# ProDoc_T527_LPDDR4_4__2024-06-06.net
KiCad netlist of a schematic drawn in EasyEDA Pro
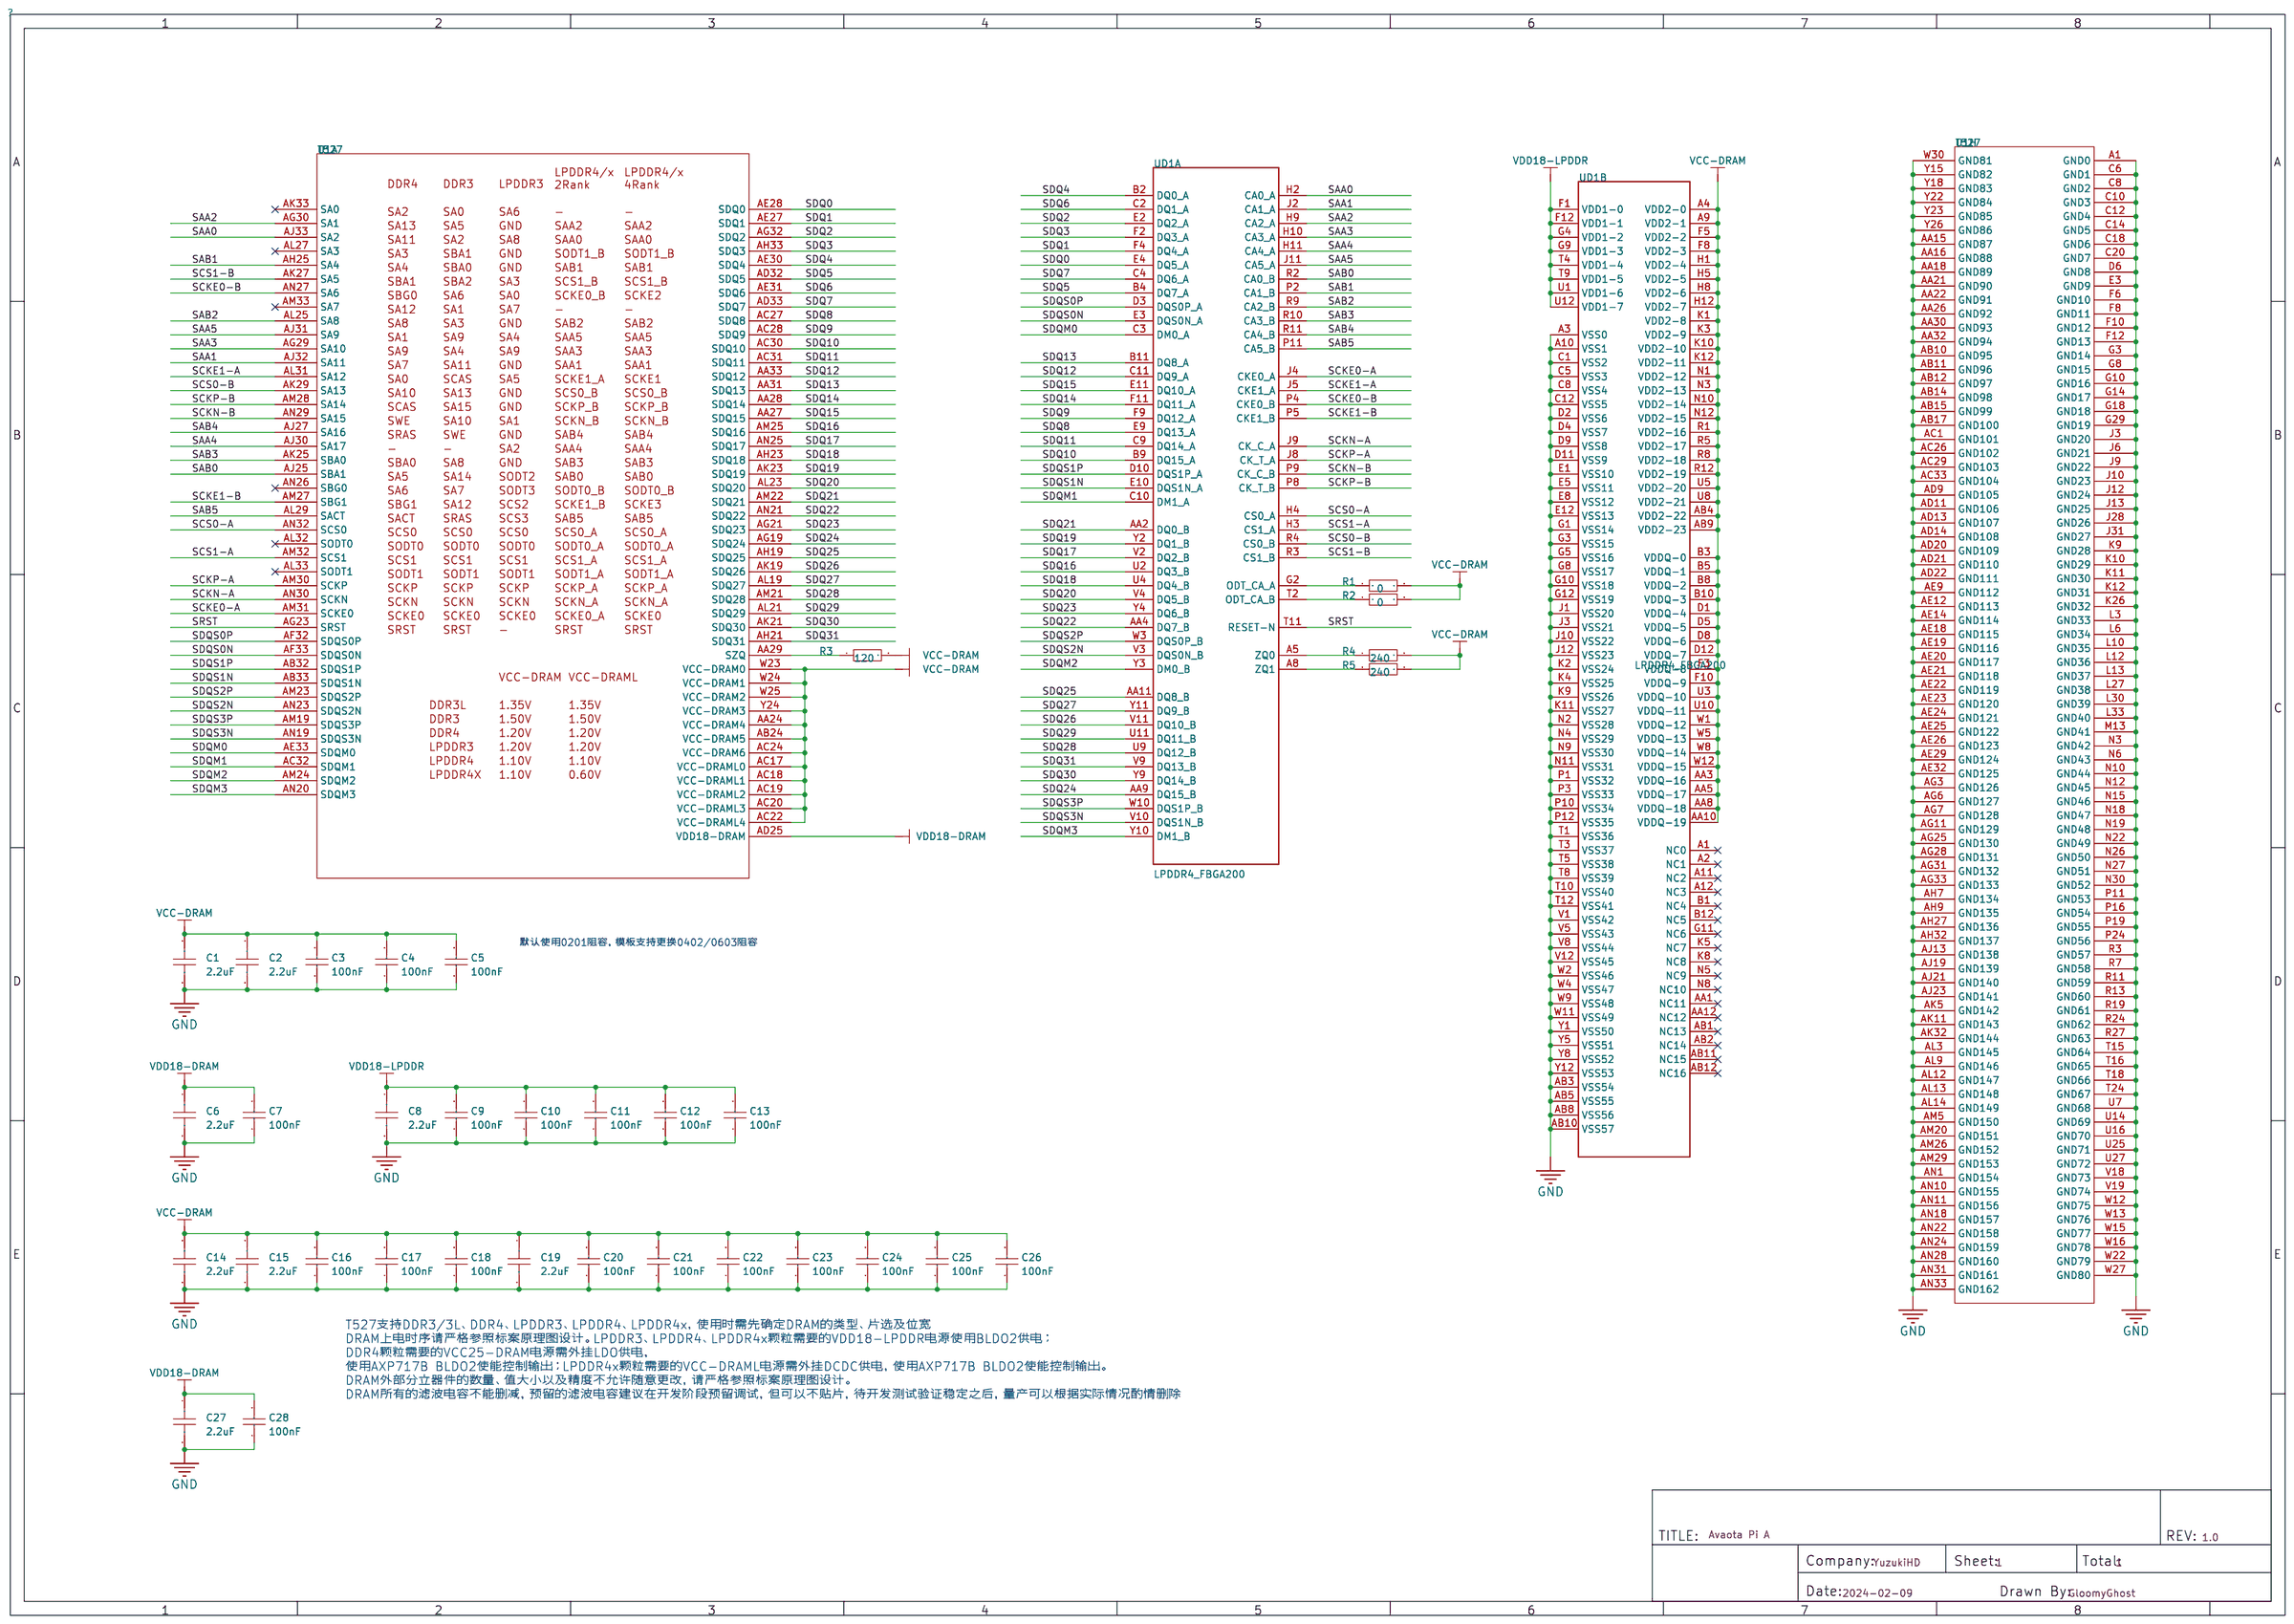
[diagram p0: schematic sheet]

(export (version "E")
  (design (tool "Eeschema 10.0.6"))
  (components
    (comp (ref "C1")
      (value "2.2uF")
      (footprint "easyedapro:C0201")
      (description "容值:2.2uF;精度:±20%;额定电压:6.3V;材质(温度系数):X5R;")
      (fields (field (name "Manufacturer Part") "0201X225M6R3NT") (field (name "Manufacturer") "FH(风华)"))
      (libsource (lib "easyedapro") (part "0201X225M6R3NT"))
    )
    (comp (ref "C2")
      (value "2.2uF")
      (footprint "easyedapro:C0201")
      (description "容值:2.2uF;精度:±20%;额定电压:6.3V;材质(温度系数):X5R;")
      (fields (field (name "Manufacturer Part") "0201X225M6R3NT") (field (name "Manufacturer") "FH(风华)"))
      (libsource (lib "easyedapro") (part "0201X225M6R3NT"))
    )
    (comp (ref "C3")
      (value "100nF")
      (footprint "easyedapro:C0201")
      (description "容值:100nF;精度:±10%;额定电压:10V;材质(温度系数):X5R;")
      (fields
        (field (name "Manufacturer Part") "GRM033R61A104KE15D")
        (field (name "Manufacturer") "muRata(村田)")
      )
      (libsource (lib "easyedapro") (part "GRM033R61A104KE15D"))
    )
    (comp (ref "C4")
      (value "100nF")
      (footprint "easyedapro:C0201")
      (description "容值:100nF;精度:±10%;额定电压:10V;材质(温度系数):X5R;")
      (fields
        (field (name "Manufacturer Part") "GRM033R61A104KE15D")
        (field (name "Manufacturer") "muRata(村田)")
      )
      (libsource (lib "easyedapro") (part "GRM033R61A104KE15D"))
    )
    (comp (ref "C5")
      (value "100nF")
      (footprint "easyedapro:C0201")
      (description "容值:100nF;精度:±10%;额定电压:10V;材质(温度系数):X5R;")
      (fields
        (field (name "Manufacturer Part") "GRM033R61A104KE15D")
        (field (name "Manufacturer") "muRata(村田)")
      )
      (libsource (lib "easyedapro") (part "GRM033R61A104KE15D"))
    )
    (comp (ref "C6")
      (value "2.2uF")
      (footprint "easyedapro:C0201")
      (description "容值:2.2uF;精度:±20%;额定电压:6.3V;材质(温度系数):X5R;")
      (fields (field (name "Manufacturer Part") "0201X225M6R3NT") (field (name "Manufacturer") "FH(风华)"))
      (libsource (lib "easyedapro") (part "0201X225M6R3NT"))
    )
    (comp (ref "C7")
      (value "100nF")
      (footprint "easyedapro:C0201")
      (description "容值:100nF;精度:±10%;额定电压:10V;材质(温度系数):X5R;")
      (fields
        (field (name "Manufacturer Part") "GRM033R61A104KE15D")
        (field (name "Manufacturer") "muRata(村田)")
      )
      (libsource (lib "easyedapro") (part "GRM033R61A104KE15D"))
    )
    (comp (ref "C8")
      (value "2.2uF")
      (footprint "easyedapro:C0201")
      (description "容值:2.2uF;精度:±20%;额定电压:6.3V;材质(温度系数):X5R;")
      (fields (field (name "Manufacturer Part") "0201X225M6R3NT") (field (name "Manufacturer") "FH(风华)"))
      (libsource (lib "easyedapro") (part "0201X225M6R3NT"))
    )
    (comp (ref "C9")
      (value "100nF")
      (footprint "easyedapro:C0201")
      (description "容值:100nF;精度:±10%;额定电压:10V;材质(温度系数):X5R;")
      (fields
        (field (name "Manufacturer Part") "GRM033R61A104KE15D")
        (field (name "Manufacturer") "muRata(村田)")
      )
      (libsource (lib "easyedapro") (part "GRM033R61A104KE15D"))
    )
    (comp (ref "C10")
      (value "100nF")
      (footprint "easyedapro:C0201")
      (description "容值:100nF;精度:±10%;额定电压:10V;材质(温度系数):X5R;")
      (fields
        (field (name "Manufacturer Part") "GRM033R61A104KE15D")
        (field (name "Manufacturer") "muRata(村田)")
      )
      (libsource (lib "easyedapro") (part "GRM033R61A104KE15D"))
    )
    (comp (ref "C11")
      (value "100nF")
      (footprint "easyedapro:C0201")
      (description "容值:100nF;精度:±10%;额定电压:10V;材质(温度系数):X5R;")
      (fields
        (field (name "Manufacturer Part") "GRM033R61A104KE15D")
        (field (name "Manufacturer") "muRata(村田)")
      )
      (libsource (lib "easyedapro") (part "GRM033R61A104KE15D"))
    )
    (comp (ref "C12")
      (value "100nF")
      (footprint "easyedapro:C0201")
      (description "容值:100nF;精度:±10%;额定电压:10V;材质(温度系数):X5R;")
      (fields
        (field (name "Manufacturer Part") "GRM033R61A104KE15D")
        (field (name "Manufacturer") "muRata(村田)")
      )
      (libsource (lib "easyedapro") (part "GRM033R61A104KE15D"))
    )
    (comp (ref "C13")
      (value "100nF")
      (footprint "easyedapro:C0201")
      (description "容值:100nF;精度:±10%;额定电压:10V;材质(温度系数):X5R;")
      (fields
        (field (name "Manufacturer Part") "GRM033R61A104KE15D")
        (field (name "Manufacturer") "muRata(村田)")
      )
      (libsource (lib "easyedapro") (part "GRM033R61A104KE15D"))
    )
    (comp (ref "C14")
      (value "2.2uF")
      (footprint "easyedapro:C0201")
      (description "容值:2.2uF;精度:±20%;额定电压:6.3V;材质(温度系数):X5R;")
      (fields (field (name "Manufacturer Part") "0201X225M6R3NT") (field (name "Manufacturer") "FH(风华)"))
      (libsource (lib "easyedapro") (part "0201X225M6R3NT"))
    )
    (comp (ref "C15")
      (value "2.2uF")
      (footprint "easyedapro:C0201")
      (description "容值:2.2uF;精度:±20%;额定电压:6.3V;材质(温度系数):X5R;")
      (fields (field (name "Manufacturer Part") "0201X225M6R3NT") (field (name "Manufacturer") "FH(风华)"))
      (libsource (lib "easyedapro") (part "0201X225M6R3NT"))
    )
    (comp (ref "C16")
      (value "100nF")
      (footprint "easyedapro:C0201")
      (description "容值:100nF;精度:±10%;额定电压:10V;材质(温度系数):X5R;")
      (fields
        (field (name "Manufacturer Part") "GRM033R61A104KE15D")
        (field (name "Manufacturer") "muRata(村田)")
      )
      (libsource (lib "easyedapro") (part "GRM033R61A104KE15D"))
    )
    (comp (ref "C17")
      (value "100nF")
      (footprint "easyedapro:C0201")
      (description "容值:100nF;精度:±10%;额定电压:10V;材质(温度系数):X5R;")
      (fields
        (field (name "Manufacturer Part") "GRM033R61A104KE15D")
        (field (name "Manufacturer") "muRata(村田)")
      )
      (libsource (lib "easyedapro") (part "GRM033R61A104KE15D"))
    )
    (comp (ref "C18")
      (value "100nF")
      (footprint "easyedapro:C0201")
      (description "容值:100nF;精度:±10%;额定电压:10V;材质(温度系数):X5R;")
      (fields
        (field (name "Manufacturer Part") "GRM033R61A104KE15D")
        (field (name "Manufacturer") "muRata(村田)")
      )
      (libsource (lib "easyedapro") (part "GRM033R61A104KE15D"))
    )
    (comp (ref "C19")
      (value "2.2uF")
      (footprint "easyedapro:C0201")
      (description "容值:2.2uF;精度:±20%;额定电压:6.3V;材质(温度系数):X5R;")
      (fields (field (name "Manufacturer Part") "0201X225M6R3NT") (field (name "Manufacturer") "FH(风华)"))
      (libsource (lib "easyedapro") (part "0201X225M6R3NT"))
    )
    (comp (ref "C20")
      (value "100nF")
      (footprint "easyedapro:C0201")
      (description "容值:100nF;精度:±10%;额定电压:10V;材质(温度系数):X5R;")
      (fields
        (field (name "Manufacturer Part") "GRM033R61A104KE15D")
        (field (name "Manufacturer") "muRata(村田)")
      )
      (libsource (lib "easyedapro") (part "GRM033R61A104KE15D"))
    )
    (comp (ref "C21")
      (value "100nF")
      (footprint "easyedapro:C0201")
      (description "容值:100nF;精度:±10%;额定电压:10V;材质(温度系数):X5R;")
      (fields
        (field (name "Manufacturer Part") "GRM033R61A104KE15D")
        (field (name "Manufacturer") "muRata(村田)")
      )
      (libsource (lib "easyedapro") (part "GRM033R61A104KE15D"))
    )
    (comp (ref "C22")
      (value "100nF")
      (footprint "easyedapro:C0201")
      (description "容值:100nF;精度:±10%;额定电压:10V;材质(温度系数):X5R;")
      (fields
        (field (name "Manufacturer Part") "GRM033R61A104KE15D")
        (field (name "Manufacturer") "muRata(村田)")
      )
      (libsource (lib "easyedapro") (part "GRM033R61A104KE15D"))
    )
    (comp (ref "C23")
      (value "100nF")
      (footprint "easyedapro:C0201")
      (description "容值:100nF;精度:±10%;额定电压:10V;材质(温度系数):X5R;")
      (fields
        (field (name "Manufacturer Part") "GRM033R61A104KE15D")
        (field (name "Manufacturer") "muRata(村田)")
      )
      (libsource (lib "easyedapro") (part "GRM033R61A104KE15D"))
    )
    (comp (ref "C24")
      (value "100nF")
      (footprint "easyedapro:C0201")
      (description "容值:100nF;精度:±10%;额定电压:10V;材质(温度系数):X5R;")
      (fields
        (field (name "Manufacturer Part") "GRM033R61A104KE15D")
        (field (name "Manufacturer") "muRata(村田)")
      )
      (libsource (lib "easyedapro") (part "GRM033R61A104KE15D"))
    )
    (comp (ref "C25")
      (value "100nF")
      (footprint "easyedapro:C0201")
      (description "容值:100nF;精度:±10%;额定电压:10V;材质(温度系数):X5R;")
      (fields
        (field (name "Manufacturer Part") "GRM033R61A104KE15D")
        (field (name "Manufacturer") "muRata(村田)")
      )
      (libsource (lib "easyedapro") (part "GRM033R61A104KE15D"))
    )
    (comp (ref "C26")
      (value "100nF")
      (footprint "easyedapro:C0201")
      (description "容值:100nF;精度:±10%;额定电压:10V;材质(温度系数):X5R;")
      (fields
        (field (name "Manufacturer Part") "GRM033R61A104KE15D")
        (field (name "Manufacturer") "muRata(村田)")
      )
      (libsource (lib "easyedapro") (part "GRM033R61A104KE15D"))
    )
    (comp (ref "C27")
      (value "2.2uF")
      (footprint "easyedapro:C0201")
      (description "容值:2.2uF;精度:±20%;额定电压:6.3V;材质(温度系数):X5R;")
      (fields (field (name "Manufacturer Part") "0201X225M6R3NT") (field (name "Manufacturer") "FH(风华)"))
      (libsource (lib "easyedapro") (part "0201X225M6R3NT"))
    )
    (comp (ref "C28")
      (value "100nF")
      (footprint "easyedapro:C0201")
      (description "容值:100nF;精度:±10%;额定电压:10V;材质(温度系数):X5R;")
      (fields
        (field (name "Manufacturer Part") "GRM033R61A104KE15D")
        (field (name "Manufacturer") "muRata(村田)")
      )
      (libsource (lib "easyedapro") (part "GRM033R61A104KE15D"))
    )
    (comp (ref "R1") (value "0") (footprint "easyedapro:R0201") (libsource (lib "easyedapro") (part "电阻")))
    (comp (ref "R2") (value "0") (footprint "easyedapro:R0201") (libsource (lib "easyedapro") (part "电阻")))
    (comp (ref "R3") (value "120") (footprint "easyedapro:R0201") (libsource (lib "easyedapro") (part "电阻")))
    (comp (ref "R4") (value "240") (footprint "easyedapro:R0201") (libsource (lib "easyedapro") (part "电阻")))
    (comp (ref "R5") (value "240") (footprint "easyedapro:R0201") (libsource (lib "easyedapro") (part "电阻")))
    (comp (ref "U1")
      (value "T527")
      (footprint "easyedapro:T527-BGA664")
      (description "Allwinner T527 SoC")
      (libsource (lib "easyedapro") (part "T527"))
    )
    (comp (ref "UD1")
      (value "LPDDR4_FBGA200")
      (footprint "easyedapro:BGA200P65_80B1000_1500H90")
      (libsource (lib "easyedapro") (part "LPDDR4_FBGA200"))
    )
  )
  (nets
    (net (code "1") (name "/SAA0") (class "Default")
      (node (ref "U1") (pin "AJ33") (pinfunction "SA2_AJ33") (pintype "input"))
      (node (ref "UD1") (pin "H2") (pinfunction "CA0_A_H2") (pintype "input"))
    )
    (net (code "2") (name "/SAA1") (class "Default")
      (node (ref "U1") (pin "AJ32") (pinfunction "SA11_AJ32") (pintype "input"))
      (node (ref "UD1") (pin "J2") (pinfunction "CA1_A_J2") (pintype "input"))
    )
    (net (code "3") (name "/SAA2") (class "Default")
      (node (ref "U1") (pin "AG30") (pinfunction "SA1_AG30") (pintype "input"))
      (node (ref "UD1") (pin "H9") (pinfunction "CA2_A_H9") (pintype "input"))
    )
    (net (code "4") (name "/SAA3") (class "Default")
      (node (ref "U1") (pin "AG29") (pinfunction "SA10_AG29") (pintype "input"))
      (node (ref "UD1") (pin "H10") (pinfunction "CA3_A_H10") (pintype "input"))
    )
    (net (code "5") (name "/SAA4") (class "Default")
      (node (ref "U1") (pin "AJ30") (pinfunction "SA17_AJ30") (pintype "input"))
      (node (ref "UD1") (pin "H11") (pinfunction "CA4_A_H11") (pintype "input"))
    )
    (net (code "6") (name "/SAA5") (class "Default")
      (node (ref "U1") (pin "AJ31") (pinfunction "SA9_AJ31") (pintype "input"))
      (node (ref "UD1") (pin "J11") (pinfunction "CA5_A_J11") (pintype "input"))
    )
    (net (code "7") (name "/SAB0") (class "Default")
      (node (ref "U1") (pin "AJ25") (pinfunction "SBA1_AJ25") (pintype "input"))
      (node (ref "UD1") (pin "R2") (pinfunction "CA0_B_R2") (pintype "input"))
    )
    (net (code "8") (name "/SAB1") (class "Default")
      (node (ref "U1") (pin "AH25") (pinfunction "SA4_AH25") (pintype "input"))
      (node (ref "UD1") (pin "P2") (pinfunction "CA1_B_P2") (pintype "input"))
    )
    (net (code "9") (name "/SAB2") (class "Default")
      (node (ref "U1") (pin "AL25") (pinfunction "SA8_AL25") (pintype "input"))
      (node (ref "UD1") (pin "R9") (pinfunction "CA2_B_R9") (pintype "input"))
    )
    (net (code "10") (name "/SAB3") (class "Default")
      (node (ref "U1") (pin "AK25") (pinfunction "SBA0_AK25") (pintype "input"))
      (node (ref "UD1") (pin "R10") (pinfunction "CA3_B_R10") (pintype "input"))
    )
    (net (code "11") (name "/SAB4") (class "Default")
      (node (ref "U1") (pin "AJ27") (pinfunction "SA16_AJ27") (pintype "input"))
      (node (ref "UD1") (pin "R11") (pinfunction "CA4_B_R11") (pintype "input"))
    )
    (net (code "12") (name "/SAB5") (class "Default")
      (node (ref "U1") (pin "AL29") (pinfunction "SACT_AL29") (pintype "input"))
      (node (ref "UD1") (pin "P11") (pinfunction "CA5_B_P11") (pintype "input"))
    )
    (net (code "13") (name "/SCKE0-A") (class "Default")
      (node (ref "U1") (pin "AM31") (pinfunction "SCKE0_AM31") (pintype "input"))
      (node (ref "UD1") (pin "J4") (pinfunction "CKE0_A_J4") (pintype "input"))
    )
    (net (code "14") (name "/SCKE0-B") (class "Default")
      (node (ref "U1") (pin "AN27") (pinfunction "SA6_AN27") (pintype "input"))
      (node (ref "UD1") (pin "P4") (pinfunction "CKE0_B_P4") (pintype "input"))
    )
    (net (code "15") (name "/SCKE1-A") (class "Default")
      (node (ref "U1") (pin "AL31") (pinfunction "SA12_AL31") (pintype "input"))
      (node (ref "UD1") (pin "J5") (pinfunction "CKE1_A_J5") (pintype "input"))
    )
    (net (code "16") (name "/SCKE1-B") (class "Default")
      (node (ref "U1") (pin "AM27") (pinfunction "SBG1_AM27") (pintype "input"))
      (node (ref "UD1") (pin "P5") (pinfunction "CKE1_B_P5") (pintype "input"))
    )
    (net (code "17") (name "/SCKN-A") (class "Default")
      (node (ref "U1") (pin "AN30") (pinfunction "SCKN_AN30") (pintype "input"))
      (node (ref "UD1") (pin "J9") (pinfunction "CK_C_A_J9") (pintype "input"))
    )
    (net (code "18") (name "/SCKN-B") (class "Default")
      (node (ref "U1") (pin "AN29") (pinfunction "SA15_AN29") (pintype "input"))
      (node (ref "UD1") (pin "P9") (pinfunction "CK_C_B_P9") (pintype "input"))
    )
    (net (code "19") (name "/SCKP-A") (class "Default")
      (node (ref "U1") (pin "AM30") (pinfunction "SCKP_AM30") (pintype "input"))
      (node (ref "UD1") (pin "J8") (pinfunction "CK_T_A_J8") (pintype "input"))
    )
    (net (code "20") (name "/SCKP-B") (class "Default")
      (node (ref "U1") (pin "AM28") (pinfunction "SA14_AM28") (pintype "input"))
      (node (ref "UD1") (pin "P8") (pinfunction "CK_T_B_P8") (pintype "input"))
    )
    (net (code "21") (name "/SCS0-A") (class "Default")
      (node (ref "U1") (pin "AN32") (pinfunction "SCS0_AN32") (pintype "input"))
      (node (ref "UD1") (pin "H4") (pinfunction "CS0_A_H4") (pintype "input"))
    )
    (net (code "22") (name "/SCS0-B") (class "Default")
      (node (ref "U1") (pin "AK29") (pinfunction "SA13_AK29") (pintype "input"))
      (node (ref "UD1") (pin "R4") (pinfunction "CS0_B_R4") (pintype "input"))
    )
    (net (code "23") (name "/SCS1-A") (class "Default")
      (node (ref "U1") (pin "AM32") (pinfunction "SCS1_AM32") (pintype "input"))
      (node (ref "UD1") (pin "H3") (pinfunction "CS1_A_H3") (pintype "input"))
    )
    (net (code "24") (name "/SCS1-B") (class "Default")
      (node (ref "U1") (pin "AK27") (pinfunction "SA5_AK27") (pintype "input"))
      (node (ref "UD1") (pin "R3") (pinfunction "CS1_B_R3") (pintype "input"))
    )
    (net (code "25") (name "/SDQ0") (class "Default")
      (node (ref "U1") (pin "AE28") (pinfunction "SDQ0_AE28") (pintype "input"))
      (node (ref "UD1") (pin "E4") (pinfunction "DQ5_A_E4") (pintype "input"))
    )
    (net (code "26") (name "/SDQ1") (class "Default")
      (node (ref "U1") (pin "AE27") (pinfunction "SDQ1_AE27") (pintype "input"))
      (node (ref "UD1") (pin "F4") (pinfunction "DQ4_A_F4") (pintype "input"))
    )
    (net (code "27") (name "/SDQ2") (class "Default")
      (node (ref "U1") (pin "AG32") (pinfunction "SDQ2_AG32") (pintype "input"))
      (node (ref "UD1") (pin "E2") (pinfunction "DQ2_A_E2") (pintype "input"))
    )
    (net (code "28") (name "/SDQ3") (class "Default")
      (node (ref "U1") (pin "AH33") (pinfunction "SDQ3_AH33") (pintype "input"))
      (node (ref "UD1") (pin "F2") (pinfunction "DQ3_A_F2") (pintype "input"))
    )
    (net (code "29") (name "/SDQ4") (class "Default")
      (node (ref "U1") (pin "AE30") (pinfunction "SDQ4_AE30") (pintype "input"))
      (node (ref "UD1") (pin "B2") (pinfunction "DQ0_A_B2") (pintype "input"))
    )
    (net (code "30") (name "/SDQ5") (class "Default")
      (node (ref "U1") (pin "AD32") (pinfunction "SDQ5_AD32") (pintype "input"))
      (node (ref "UD1") (pin "B4") (pinfunction "DQ7_A_B4") (pintype "input"))
    )
    (net (code "31") (name "/SDQ6") (class "Default")
      (node (ref "U1") (pin "AE31") (pinfunction "SDQ6_AE31") (pintype "input"))
      (node (ref "UD1") (pin "C2") (pinfunction "DQ1_A_C2") (pintype "input"))
    )
    (net (code "32") (name "/SDQ7") (class "Default")
      (node (ref "U1") (pin "AD33") (pinfunction "SDQ7_AD33") (pintype "input"))
      (node (ref "UD1") (pin "C4") (pinfunction "DQ6_A_C4") (pintype "input"))
    )
    (net (code "33") (name "/SDQ8") (class "Default")
      (node (ref "U1") (pin "AC27") (pinfunction "SDQ8_AC27") (pintype "input"))
      (node (ref "UD1") (pin "E9") (pinfunction "DQ13_A_E9") (pintype "input"))
    )
    (net (code "34") (name "/SDQ9") (class "Default")
      (node (ref "U1") (pin "AC28") (pinfunction "SDQ9_AC28") (pintype "input"))
      (node (ref "UD1") (pin "F9") (pinfunction "DQ12_A_F9") (pintype "input"))
    )
    (net (code "35") (name "/SDQ10") (class "Default")
      (node (ref "U1") (pin "AC30") (pinfunction "SDQ10_AC30") (pintype "input"))
      (node (ref "UD1") (pin "B9") (pinfunction "DQ15_A_B9") (pintype "input"))
    )
    (net (code "36") (name "/SDQ11") (class "Default")
      (node (ref "U1") (pin "AC31") (pinfunction "SDQ11_AC31") (pintype "input"))
      (node (ref "UD1") (pin "C9") (pinfunction "DQ14_A_C9") (pintype "input"))
    )
    (net (code "37") (name "/SDQ12") (class "Default")
      (node (ref "U1") (pin "AA33") (pinfunction "SDQ12_AA33") (pintype "input"))
      (node (ref "UD1") (pin "C11") (pinfunction "DQ9_A_C11") (pintype "input"))
    )
    (net (code "38") (name "/SDQ13") (class "Default")
      (node (ref "U1") (pin "AA31") (pinfunction "SDQ13_AA31") (pintype "input"))
      (node (ref "UD1") (pin "B11") (pinfunction "DQ8_A_B11") (pintype "input"))
    )
    (net (code "39") (name "/SDQ14") (class "Default")
      (node (ref "U1") (pin "AA28") (pinfunction "SDQ14_AA28") (pintype "input"))
      (node (ref "UD1") (pin "F11") (pinfunction "DQ11_A_F11") (pintype "input"))
    )
    (net (code "40") (name "/SDQ15") (class "Default")
      (node (ref "U1") (pin "AA27") (pinfunction "SDQ15_AA27") (pintype "input"))
      (node (ref "UD1") (pin "E11") (pinfunction "DQ10_A_E11") (pintype "input"))
    )
    (net (code "41") (name "/SDQ16") (class "Default")
      (node (ref "U1") (pin "AM25") (pinfunction "SDQ16_AM25") (pintype "input"))
      (node (ref "UD1") (pin "U2") (pinfunction "DQ3_B_U2") (pintype "input"))
    )
    (net (code "42") (name "/SDQ17") (class "Default")
      (node (ref "U1") (pin "AN25") (pinfunction "SDQ17_AN25") (pintype "input"))
      (node (ref "UD1") (pin "V2") (pinfunction "DQ2_B_V2") (pintype "input"))
    )
    (net (code "43") (name "/SDQ18") (class "Default")
      (node (ref "U1") (pin "AH23") (pinfunction "SDQ18_AH23") (pintype "input"))
      (node (ref "UD1") (pin "U4") (pinfunction "DQ4_B_U4") (pintype "input"))
    )
    (net (code "44") (name "/SDQ19") (class "Default")
      (node (ref "U1") (pin "AK23") (pinfunction "SDQ19_AK23") (pintype "input"))
      (node (ref "UD1") (pin "Y2") (pinfunction "DQ1_B_Y2") (pintype "input"))
    )
    (net (code "45") (name "/SDQ20") (class "Default")
      (node (ref "U1") (pin "AL23") (pinfunction "SDQ20_AL23") (pintype "input"))
      (node (ref "UD1") (pin "V4") (pinfunction "DQ5_B_V4") (pintype "input"))
    )
    (net (code "46") (name "/SDQ21") (class "Default")
      (node (ref "U1") (pin "AM22") (pinfunction "SDQ21_AM22") (pintype "input"))
      (node (ref "UD1") (pin "AA2") (pinfunction "DQ0_B_AA2") (pintype "input"))
    )
    (net (code "47") (name "/SDQ22") (class "Default")
      (node (ref "U1") (pin "AN21") (pinfunction "SDQ22_AN21") (pintype "input"))
      (node (ref "UD1") (pin "AA4") (pinfunction "DQ7_B_AA4") (pintype "input"))
    )
    (net (code "48") (name "/SDQ23") (class "Default")
      (node (ref "U1") (pin "AG21") (pinfunction "SDQ23_AG21") (pintype "input"))
      (node (ref "UD1") (pin "Y4") (pinfunction "DQ6_B_Y4") (pintype "input"))
    )
    (net (code "49") (name "/SDQ24") (class "Default")
      (node (ref "U1") (pin "AG19") (pinfunction "SDQ24_AG19") (pintype "input"))
      (node (ref "UD1") (pin "AA9") (pinfunction "DQ15_B_AA9") (pintype "input"))
    )
    (net (code "50") (name "/SDQ25") (class "Default")
      (node (ref "U1") (pin "AH19") (pinfunction "SDQ25_AH19") (pintype "input"))
      (node (ref "UD1") (pin "AA11") (pinfunction "DQ8_B_AA11") (pintype "input"))
    )
    (net (code "51") (name "/SDQ26") (class "Default")
      (node (ref "U1") (pin "AK19") (pinfunction "SDQ26_AK19") (pintype "input"))
      (node (ref "UD1") (pin "V11") (pinfunction "DQ10_B_V11") (pintype "input"))
    )
    (net (code "52") (name "/SDQ27") (class "Default")
      (node (ref "U1") (pin "AL19") (pinfunction "SDQ27_AL19") (pintype "input"))
      (node (ref "UD1") (pin "Y11") (pinfunction "DQ9_B_Y11") (pintype "input"))
    )
    (net (code "53") (name "/SDQ28") (class "Default")
      (node (ref "U1") (pin "AM21") (pinfunction "SDQ28_AM21") (pintype "input"))
      (node (ref "UD1") (pin "U9") (pinfunction "DQ12_B_U9") (pintype "input"))
    )
    (net (code "54") (name "/SDQ29") (class "Default")
      (node (ref "U1") (pin "AL21") (pinfunction "SDQ29_AL21") (pintype "input"))
      (node (ref "UD1") (pin "U11") (pinfunction "DQ11_B_U11") (pintype "input"))
    )
    (net (code "55") (name "/SDQ30") (class "Default")
      (node (ref "U1") (pin "AK21") (pinfunction "SDQ30_AK21") (pintype "input"))
      (node (ref "UD1") (pin "Y9") (pinfunction "DQ14_B_Y9") (pintype "input"))
    )
    (net (code "56") (name "/SDQ31") (class "Default")
      (node (ref "U1") (pin "AH21") (pinfunction "SDQ31_AH21") (pintype "input"))
      (node (ref "UD1") (pin "V9") (pinfunction "DQ13_B_V9") (pintype "input"))
    )
    (net (code "57") (name "/SDQM0") (class "Default")
      (node (ref "U1") (pin "AE33") (pinfunction "SDQM0_AE33") (pintype "input"))
      (node (ref "UD1") (pin "C3") (pinfunction "DM0_A_C3") (pintype "input"))
    )
    (net (code "58") (name "/SDQM1") (class "Default")
      (node (ref "U1") (pin "AC32") (pinfunction "SDQM1_AC32") (pintype "input"))
      (node (ref "UD1") (pin "C10") (pinfunction "DM1_A_C10") (pintype "input"))
    )
    (net (code "59") (name "/SDQM2") (class "Default")
      (node (ref "U1") (pin "AM24") (pinfunction "SDQM2_AM24") (pintype "input"))
      (node (ref "UD1") (pin "Y3") (pinfunction "DM0_B_Y3") (pintype "input"))
    )
    (net (code "60") (name "/SDQM3") (class "Default")
      (node (ref "U1") (pin "AN20") (pinfunction "SDQM3_AN20") (pintype "input"))
      (node (ref "UD1") (pin "Y10") (pinfunction "DM1_B_Y10") (pintype "input"))
    )
    (net (code "61") (name "/SDQS0N") (class "Default")
      (node (ref "U1") (pin "AF33") (pinfunction "SDQS0N_AF33") (pintype "input"))
      (node (ref "UD1") (pin "E3") (pinfunction "DQS0N_A_E3") (pintype "input"))
    )
    (net (code "62") (name "/SDQS0P") (class "Default")
      (node (ref "U1") (pin "AF32") (pinfunction "SDQS0P_AF32") (pintype "input"))
      (node (ref "UD1") (pin "D3") (pinfunction "DQS0P_A_D3") (pintype "input"))
    )
    (net (code "63") (name "/SDQS1N") (class "Default")
      (node (ref "U1") (pin "AB33") (pinfunction "SDQS1N_AB33") (pintype "input"))
      (node (ref "UD1") (pin "E10") (pinfunction "DQS1N_A_E10") (pintype "input"))
    )
    (net (code "64") (name "/SDQS1P") (class "Default")
      (node (ref "U1") (pin "AB32") (pinfunction "SDQS1P_AB32") (pintype "input"))
      (node (ref "UD1") (pin "D10") (pinfunction "DQS1P_A_D10") (pintype "input"))
    )
    (net (code "65") (name "/SDQS2N") (class "Default")
      (node (ref "U1") (pin "AN23") (pinfunction "SDQS2N_AN23") (pintype "input"))
      (node (ref "UD1") (pin "V3") (pinfunction "DQS0N_B_V3") (pintype "input"))
    )
    (net (code "66") (name "/SDQS2P") (class "Default")
      (node (ref "U1") (pin "AM23") (pinfunction "SDQS2P_AM23") (pintype "input"))
      (node (ref "UD1") (pin "W3") (pinfunction "DQS0P_B_W3") (pintype "input"))
    )
    (net (code "67") (name "/SDQS3N") (class "Default")
      (node (ref "U1") (pin "AN19") (pinfunction "SDQS3N_AN19") (pintype "input"))
      (node (ref "UD1") (pin "V10") (pinfunction "DQS1N_B_V10") (pintype "input"))
    )
    (net (code "68") (name "/SDQS3P") (class "Default")
      (node (ref "U1") (pin "AM19") (pinfunction "SDQS3P_AM19") (pintype "input"))
      (node (ref "UD1") (pin "W10") (pinfunction "DQS1P_B_W10") (pintype "input"))
    )
    (net (code "69") (name "/SRST") (class "Default")
      (node (ref "U1") (pin "AG23") (pinfunction "SRST_AG23") (pintype "input"))
      (node (ref "UD1") (pin "T11") (pinfunction "RESET-N_T11") (pintype "input"))
    )
    (net (code "70") (name "GND") (class "Default")
      (node (ref "C1") (pin "2") (pinfunction "2_2") (pintype "input"))
      (node (ref "C10") (pin "1") (pinfunction "1_1") (pintype "input"))
      (node (ref "C11") (pin "1") (pinfunction "1_1") (pintype "input"))
      (node (ref "C12") (pin "1") (pinfunction "1_1") (pintype "input"))
      (node (ref "C13") (pin "1") (pinfunction "1_1") (pintype "input"))
      (node (ref "C14") (pin "2") (pinfunction "2_2") (pintype "input"))
      (node (ref "C15") (pin "2") (pinfunction "2_2") (pintype "input"))
      (node (ref "C16") (pin "1") (pinfunction "1_1") (pintype "input"))
      (node (ref "C17") (pin "1") (pinfunction "1_1") (pintype "input"))
      (node (ref "C18") (pin "1") (pinfunction "1_1") (pintype "input"))
      (node (ref "C19") (pin "2") (pinfunction "2_2") (pintype "input"))
      (node (ref "C2") (pin "2") (pinfunction "2_2") (pintype "input"))
      (node (ref "C20") (pin "1") (pinfunction "1_1") (pintype "input"))
      (node (ref "C21") (pin "1") (pinfunction "1_1") (pintype "input"))
      (node (ref "C22") (pin "1") (pinfunction "1_1") (pintype "input"))
      (node (ref "C23") (pin "1") (pinfunction "1_1") (pintype "input"))
      (node (ref "C24") (pin "1") (pinfunction "1_1") (pintype "input"))
      (node (ref "C25") (pin "1") (pinfunction "1_1") (pintype "input"))
      (node (ref "C26") (pin "1") (pinfunction "1_1") (pintype "input"))
      (node (ref "C27") (pin "2") (pinfunction "2_2") (pintype "input"))
      (node (ref "C28") (pin "1") (pinfunction "1_1") (pintype "input"))
      (node (ref "C3") (pin "1") (pinfunction "1_1") (pintype "input"))
      (node (ref "C4") (pin "1") (pinfunction "1_1") (pintype "input"))
      (node (ref "C5") (pin "1") (pinfunction "1_1") (pintype "input"))
      (node (ref "C6") (pin "2") (pinfunction "2_2") (pintype "input"))
      (node (ref "C7") (pin "1") (pinfunction "1_1") (pintype "input"))
      (node (ref "C8") (pin "2") (pinfunction "2_2") (pintype "input"))
      (node (ref "C9") (pin "1") (pinfunction "1_1") (pintype "input"))
      (node (ref "U1") (pin "A1") (pinfunction "GND0_A1") (pintype "input"))
      (node (ref "U1") (pin "AA15") (pinfunction "GND87_AA15") (pintype "input"))
      (node (ref "U1") (pin "AA16") (pinfunction "GND88_AA16") (pintype "input"))
      (node (ref "U1") (pin "AA18") (pinfunction "GND89_AA18") (pintype "input"))
      (node (ref "U1") (pin "AA21") (pinfunction "GND90_AA21") (pintype "input"))
      (node (ref "U1") (pin "AA22") (pinfunction "GND91_AA22") (pintype "input"))
      (node (ref "U1") (pin "AA26") (pinfunction "GND92_AA26") (pintype "input"))
      (node (ref "U1") (pin "AA30") (pinfunction "GND93_AA30") (pintype "input"))
      (node (ref "U1") (pin "AA32") (pinfunction "GND94_AA32") (pintype "input"))
      (node (ref "U1") (pin "AB10") (pinfunction "GND95_AB10") (pintype "input"))
      (node (ref "U1") (pin "AB11") (pinfunction "GND96_AB11") (pintype "input"))
      (node (ref "U1") (pin "AB12") (pinfunction "GND97_AB12") (pintype "input"))
      (node (ref "U1") (pin "AB14") (pinfunction "GND98_AB14") (pintype "input"))
      (node (ref "U1") (pin "AB15") (pinfunction "GND99_AB15") (pintype "input"))
      (node (ref "U1") (pin "AB17") (pinfunction "GND100_AB17") (pintype "input"))
      (node (ref "U1") (pin "AC1") (pinfunction "GND101_AC1") (pintype "input"))
      (node (ref "U1") (pin "AC26") (pinfunction "GND102_AC26") (pintype "input"))
      (node (ref "U1") (pin "AC29") (pinfunction "GND103_AC29") (pintype "input"))
      (node (ref "U1") (pin "AC33") (pinfunction "GND104_AC33") (pintype "input"))
      (node (ref "U1") (pin "AD11") (pinfunction "GND106_AD11") (pintype "input"))
      (node (ref "U1") (pin "AD13") (pinfunction "GND107_AD13") (pintype "input"))
      (node (ref "U1") (pin "AD14") (pinfunction "GND108_AD14") (pintype "input"))
      (node (ref "U1") (pin "AD20") (pinfunction "GND109_AD20") (pintype "input"))
      (node (ref "U1") (pin "AD21") (pinfunction "GND110_AD21") (pintype "input"))
      (node (ref "U1") (pin "AD22") (pinfunction "GND111_AD22") (pintype "input"))
      (node (ref "U1") (pin "AD9") (pinfunction "GND105_AD9") (pintype "input"))
      (node (ref "U1") (pin "AE12") (pinfunction "GND113_AE12") (pintype "input"))
      (node (ref "U1") (pin "AE14") (pinfunction "GND114_AE14") (pintype "input"))
      (node (ref "U1") (pin "AE18") (pinfunction "GND115_AE18") (pintype "input"))
      (node (ref "U1") (pin "AE19") (pinfunction "GND116_AE19") (pintype "input"))
      (node (ref "U1") (pin "AE20") (pinfunction "GND117_AE20") (pintype "input"))
      (node (ref "U1") (pin "AE21") (pinfunction "GND118_AE21") (pintype "input"))
      (node (ref "U1") (pin "AE22") (pinfunction "GND119_AE22") (pintype "input"))
      (node (ref "U1") (pin "AE23") (pinfunction "GND120_AE23") (pintype "input"))
      (node (ref "U1") (pin "AE24") (pinfunction "GND121_AE24") (pintype "input"))
      (node (ref "U1") (pin "AE25") (pinfunction "GND122_AE25") (pintype "input"))
      (node (ref "U1") (pin "AE26") (pinfunction "GND123_AE26") (pintype "input"))
      (node (ref "U1") (pin "AE29") (pinfunction "GND124_AE29") (pintype "input"))
      (node (ref "U1") (pin "AE32") (pinfunction "GND125_AE32") (pintype "input"))
      (node (ref "U1") (pin "AE9") (pinfunction "GND112_AE9") (pintype "input"))
      (node (ref "U1") (pin "AG11") (pinfunction "GND129_AG11") (pintype "input"))
      (node (ref "U1") (pin "AG25") (pinfunction "GND130_AG25") (pintype "input"))
      (node (ref "U1") (pin "AG28") (pinfunction "GND131_AG28") (pintype "input"))
      (node (ref "U1") (pin "AG3") (pinfunction "GND126_AG3") (pintype "input"))
      (node (ref "U1") (pin "AG31") (pinfunction "GND132_AG31") (pintype "input"))
      (node (ref "U1") (pin "AG33") (pinfunction "GND133_AG33") (pintype "input"))
      (node (ref "U1") (pin "AG6") (pinfunction "GND127_AG6") (pintype "input"))
      (node (ref "U1") (pin "AG7") (pinfunction "GND128_AG7") (pintype "input"))
      (node (ref "U1") (pin "AH27") (pinfunction "GND136_AH27") (pintype "input"))
      (node (ref "U1") (pin "AH32") (pinfunction "GND137_AH32") (pintype "input"))
      (node (ref "U1") (pin "AH7") (pinfunction "GND134_AH7") (pintype "input"))
      (node (ref "U1") (pin "AH9") (pinfunction "GND135_AH9") (pintype "input"))
      (node (ref "U1") (pin "AJ13") (pinfunction "GND138_AJ13") (pintype "input"))
      (node (ref "U1") (pin "AJ19") (pinfunction "GND139_AJ19") (pintype "input"))
      (node (ref "U1") (pin "AJ21") (pinfunction "GND140_AJ21") (pintype "input"))
      (node (ref "U1") (pin "AJ23") (pinfunction "GND141_AJ23") (pintype "input"))
      (node (ref "U1") (pin "AK11") (pinfunction "GND143_AK11") (pintype "input"))
      (node (ref "U1") (pin "AK32") (pinfunction "GND144_AK32") (pintype "input"))
      (node (ref "U1") (pin "AK5") (pinfunction "GND142_AK5") (pintype "input"))
      (node (ref "U1") (pin "AL12") (pinfunction "GND147_AL12") (pintype "input"))
      (node (ref "U1") (pin "AL13") (pinfunction "GND148_AL13") (pintype "input"))
      (node (ref "U1") (pin "AL14") (pinfunction "GND149_AL14") (pintype "input"))
      (node (ref "U1") (pin "AL3") (pinfunction "GND145_AL3") (pintype "input"))
      (node (ref "U1") (pin "AL9") (pinfunction "GND146_AL9") (pintype "input"))
      (node (ref "U1") (pin "AM20") (pinfunction "GND151_AM20") (pintype "input"))
      (node (ref "U1") (pin "AM26") (pinfunction "GND152_AM26") (pintype "input"))
      (node (ref "U1") (pin "AM29") (pinfunction "GND153_AM29") (pintype "input"))
      (node (ref "U1") (pin "AM5") (pinfunction "GND150_AM5") (pintype "input"))
      (node (ref "U1") (pin "AN1") (pinfunction "GND154_AN1") (pintype "input"))
      (node (ref "U1") (pin "AN10") (pinfunction "GND155_AN10") (pintype "input"))
      (node (ref "U1") (pin "AN11") (pinfunction "GND156_AN11") (pintype "input"))
      (node (ref "U1") (pin "AN18") (pinfunction "GND157_AN18") (pintype "input"))
      (node (ref "U1") (pin "AN22") (pinfunction "GND158_AN22") (pintype "input"))
      (node (ref "U1") (pin "AN24") (pinfunction "GND159_AN24") (pintype "input"))
      (node (ref "U1") (pin "AN28") (pinfunction "GND160_AN28") (pintype "input"))
      (node (ref "U1") (pin "AN31") (pinfunction "GND161_AN31") (pintype "input"))
      (node (ref "U1") (pin "AN33") (pinfunction "GND162_AN33") (pintype "input"))
      (node (ref "U1") (pin "C10") (pinfunction "GND3_C10") (pintype "input"))
      (node (ref "U1") (pin "C12") (pinfunction "GND4_C12") (pintype "input"))
      (node (ref "U1") (pin "C14") (pinfunction "GND5_C14") (pintype "input"))
      (node (ref "U1") (pin "C18") (pinfunction "GND6_C18") (pintype "input"))
      (node (ref "U1") (pin "C20") (pinfunction "GND7_C20") (pintype "input"))
      (node (ref "U1") (pin "C6") (pinfunction "GND1_C6") (pintype "input"))
      (node (ref "U1") (pin "C8") (pinfunction "GND2_C8") (pintype "input"))
      (node (ref "U1") (pin "D6") (pinfunction "GND8_D6") (pintype "input"))
      (node (ref "U1") (pin "E3") (pinfunction "GND9_E3") (pintype "input"))
      (node (ref "U1") (pin "F10") (pinfunction "GND12_F10") (pintype "input"))
      (node (ref "U1") (pin "F12") (pinfunction "GND13_F12") (pintype "input"))
      (node (ref "U1") (pin "F6") (pinfunction "GND10_F6") (pintype "input"))
      (node (ref "U1") (pin "F8") (pinfunction "GND11_F8") (pintype "input"))
      (node (ref "U1") (pin "G10") (pinfunction "GND16_G10") (pintype "input"))
      (node (ref "U1") (pin "G14") (pinfunction "GND17_G14") (pintype "input"))
      (node (ref "U1") (pin "G18") (pinfunction "GND18_G18") (pintype "input"))
      (node (ref "U1") (pin "G29") (pinfunction "GND19_G29") (pintype "input"))
      (node (ref "U1") (pin "G3") (pinfunction "GND14_G3") (pintype "input"))
      (node (ref "U1") (pin "G8") (pinfunction "GND15_G8") (pintype "input"))
      (node (ref "U1") (pin "J10") (pinfunction "GND23_J10") (pintype "input"))
      (node (ref "U1") (pin "J12") (pinfunction "GND24_J12") (pintype "input"))
      (node (ref "U1") (pin "J13") (pinfunction "GND25_J13") (pintype "input"))
      (node (ref "U1") (pin "J28") (pinfunction "GND26_J28") (pintype "input"))
      (node (ref "U1") (pin "J3") (pinfunction "GND20_J3") (pintype "input"))
      (node (ref "U1") (pin "J31") (pinfunction "GND27_J31") (pintype "input"))
      (node (ref "U1") (pin "J6") (pinfunction "GND21_J6") (pintype "input"))
      (node (ref "U1") (pin "J9") (pinfunction "GND22_J9") (pintype "input"))
      (node (ref "U1") (pin "K10") (pinfunction "GND29_K10") (pintype "input"))
      (node (ref "U1") (pin "K11") (pinfunction "GND30_K11") (pintype "input"))
      (node (ref "U1") (pin "K12") (pinfunction "GND31_K12") (pintype "input"))
      (node (ref "U1") (pin "K26") (pinfunction "GND32_K26") (pintype "input"))
      (node (ref "U1") (pin "K9") (pinfunction "GND28_K9") (pintype "input"))
      (node (ref "U1") (pin "L10") (pinfunction "GND35_L10") (pintype "input"))
      (node (ref "U1") (pin "L12") (pinfunction "GND36_L12") (pintype "input"))
      (node (ref "U1") (pin "L13") (pinfunction "GND37_L13") (pintype "input"))
      (node (ref "U1") (pin "L27") (pinfunction "GND38_L27") (pintype "input"))
      (node (ref "U1") (pin "L3") (pinfunction "GND33_L3") (pintype "input"))
      (node (ref "U1") (pin "L30") (pinfunction "GND39_L30") (pintype "input"))
      (node (ref "U1") (pin "L33") (pinfunction "GND40_L33") (pintype "input"))
      (node (ref "U1") (pin "L6") (pinfunction "GND34_L6") (pintype "input"))
      (node (ref "U1") (pin "M13") (pinfunction "GND41_M13") (pintype "input"))
      (node (ref "U1") (pin "N10") (pinfunction "GND44_N10") (pintype "input"))
      (node (ref "U1") (pin "N12") (pinfunction "GND45_N12") (pintype "input"))
      (node (ref "U1") (pin "N15") (pinfunction "GND46_N15") (pintype "input"))
      (node (ref "U1") (pin "N18") (pinfunction "GND47_N18") (pintype "input"))
      (node (ref "U1") (pin "N19") (pinfunction "GND48_N19") (pintype "input"))
      (node (ref "U1") (pin "N22") (pinfunction "GND49_N22") (pintype "input"))
      (node (ref "U1") (pin "N26") (pinfunction "GND50_N26") (pintype "input"))
      (node (ref "U1") (pin "N27") (pinfunction "GND51_N27") (pintype "input"))
      (node (ref "U1") (pin "N3") (pinfunction "GND42_N3") (pintype "input"))
      (node (ref "U1") (pin "N30") (pinfunction "GND52_N30") (pintype "input"))
      (node (ref "U1") (pin "N6") (pinfunction "GND43_N6") (pintype "input"))
      (node (ref "U1") (pin "P11") (pinfunction "GND53_P11") (pintype "input"))
      (node (ref "U1") (pin "P16") (pinfunction "GND54_P16") (pintype "input"))
      (node (ref "U1") (pin "P19") (pinfunction "GND55_P19") (pintype "input"))
      (node (ref "U1") (pin "P24") (pinfunction "GND56_P24") (pintype "input"))
      (node (ref "U1") (pin "R11") (pinfunction "GND59_R11") (pintype "input"))
      (node (ref "U1") (pin "R13") (pinfunction "GND60_R13") (pintype "input"))
      (node (ref "U1") (pin "R19") (pinfunction "GND61_R19") (pintype "input"))
      (node (ref "U1") (pin "R24") (pinfunction "GND62_R24") (pintype "input"))
      (node (ref "U1") (pin "R27") (pinfunction "GND63_R27") (pintype "input"))
      (node (ref "U1") (pin "R3") (pinfunction "GND57_R3") (pintype "input"))
      (node (ref "U1") (pin "R7") (pinfunction "GND58_R7") (pintype "input"))
      (node (ref "U1") (pin "T15") (pinfunction "GND64_T15") (pintype "input"))
      (node (ref "U1") (pin "T16") (pinfunction "GND65_T16") (pintype "input"))
      (node (ref "U1") (pin "T18") (pinfunction "GND66_T18") (pintype "input"))
      (node (ref "U1") (pin "T24") (pinfunction "GND67_T24") (pintype "input"))
      (node (ref "U1") (pin "U14") (pinfunction "GND69_U14") (pintype "input"))
      (node (ref "U1") (pin "U16") (pinfunction "GND70_U16") (pintype "input"))
      (node (ref "U1") (pin "U25") (pinfunction "GND71_U25") (pintype "input"))
      (node (ref "U1") (pin "U27") (pinfunction "GND72_U27") (pintype "input"))
      (node (ref "U1") (pin "U7") (pinfunction "GND68_U7") (pintype "input"))
      (node (ref "U1") (pin "V18") (pinfunction "GND73_V18") (pintype "input"))
      (node (ref "U1") (pin "V19") (pinfunction "GND74_V19") (pintype "input"))
      (node (ref "U1") (pin "W12") (pinfunction "GND75_W12") (pintype "input"))
      (node (ref "U1") (pin "W13") (pinfunction "GND76_W13") (pintype "input"))
      (node (ref "U1") (pin "W15") (pinfunction "GND77_W15") (pintype "input"))
      (node (ref "U1") (pin "W16") (pinfunction "GND78_W16") (pintype "input"))
      (node (ref "U1") (pin "W22") (pinfunction "GND79_W22") (pintype "input"))
      (node (ref "U1") (pin "W27") (pinfunction "GND80_W27") (pintype "input"))
      (node (ref "U1") (pin "W30") (pinfunction "GND81_W30") (pintype "input"))
      (node (ref "U1") (pin "Y15") (pinfunction "GND82_Y15") (pintype "input"))
      (node (ref "U1") (pin "Y18") (pinfunction "GND83_Y18") (pintype "input"))
      (node (ref "U1") (pin "Y22") (pinfunction "GND84_Y22") (pintype "input"))
      (node (ref "U1") (pin "Y23") (pinfunction "GND85_Y23") (pintype "input"))
      (node (ref "U1") (pin "Y26") (pinfunction "GND86_Y26") (pintype "input"))
      (node (ref "UD1") (pin "A10") (pinfunction "VSS1_A10") (pintype "input"))
      (node (ref "UD1") (pin "A3") (pinfunction "VSS0_A3") (pintype "input"))
      (node (ref "UD1") (pin "AB10") (pinfunction "VSS57_AB10") (pintype "input"))
      (node (ref "UD1") (pin "AB3") (pinfunction "VSS54_AB3") (pintype "input"))
      (node (ref "UD1") (pin "AB5") (pinfunction "VSS55_AB5") (pintype "input"))
      (node (ref "UD1") (pin "AB8") (pinfunction "VSS56_AB8") (pintype "input"))
      (node (ref "UD1") (pin "C1") (pinfunction "VSS2_C1") (pintype "input"))
      (node (ref "UD1") (pin "C12") (pinfunction "VSS5_C12") (pintype "input"))
      (node (ref "UD1") (pin "C5") (pinfunction "VSS3_C5") (pintype "input"))
      (node (ref "UD1") (pin "C8") (pinfunction "VSS4_C8") (pintype "input"))
      (node (ref "UD1") (pin "D11") (pinfunction "VSS9_D11") (pintype "input"))
      (node (ref "UD1") (pin "D2") (pinfunction "VSS6_D2") (pintype "input"))
      (node (ref "UD1") (pin "D4") (pinfunction "VSS7_D4") (pintype "input"))
      (node (ref "UD1") (pin "D9") (pinfunction "VSS8_D9") (pintype "input"))
      (node (ref "UD1") (pin "E1") (pinfunction "VSS10_E1") (pintype "input"))
      (node (ref "UD1") (pin "E12") (pinfunction "VSS13_E12") (pintype "input"))
      (node (ref "UD1") (pin "E5") (pinfunction "VSS11_E5") (pintype "input"))
      (node (ref "UD1") (pin "E8") (pinfunction "VSS12_E8") (pintype "input"))
      (node (ref "UD1") (pin "G1") (pinfunction "VSS14_G1") (pintype "input"))
      (node (ref "UD1") (pin "G10") (pinfunction "VSS18_G10") (pintype "input"))
      (node (ref "UD1") (pin "G12") (pinfunction "VSS19_G12") (pintype "input"))
      (node (ref "UD1") (pin "G3") (pinfunction "VSS15_G3") (pintype "input"))
      (node (ref "UD1") (pin "G5") (pinfunction "VSS16_G5") (pintype "input"))
      (node (ref "UD1") (pin "G8") (pinfunction "VSS17_G8") (pintype "input"))
      (node (ref "UD1") (pin "J1") (pinfunction "VSS20_J1") (pintype "input"))
      (node (ref "UD1") (pin "J10") (pinfunction "VSS22_J10") (pintype "input"))
      (node (ref "UD1") (pin "J12") (pinfunction "VSS23_J12") (pintype "input"))
      (node (ref "UD1") (pin "J3") (pinfunction "VSS21_J3") (pintype "input"))
      (node (ref "UD1") (pin "K11") (pinfunction "VSS27_K11") (pintype "input"))
      (node (ref "UD1") (pin "K2") (pinfunction "VSS24_K2") (pintype "input"))
      (node (ref "UD1") (pin "K4") (pinfunction "VSS25_K4") (pintype "input"))
      (node (ref "UD1") (pin "K9") (pinfunction "VSS26_K9") (pintype "input"))
      (node (ref "UD1") (pin "N11") (pinfunction "VSS31_N11") (pintype "input"))
      (node (ref "UD1") (pin "N2") (pinfunction "VSS28_N2") (pintype "input"))
      (node (ref "UD1") (pin "N4") (pinfunction "VSS29_N4") (pintype "input"))
      (node (ref "UD1") (pin "N9") (pinfunction "VSS30_N9") (pintype "input"))
      (node (ref "UD1") (pin "P1") (pinfunction "VSS32_P1") (pintype "input"))
      (node (ref "UD1") (pin "P10") (pinfunction "VSS34_P10") (pintype "input"))
      (node (ref "UD1") (pin "P12") (pinfunction "VSS35_P12") (pintype "input"))
      (node (ref "UD1") (pin "P3") (pinfunction "VSS33_P3") (pintype "input"))
      (node (ref "UD1") (pin "T1") (pinfunction "VSS36_T1") (pintype "input"))
      (node (ref "UD1") (pin "T10") (pinfunction "VSS40_T10") (pintype "input"))
      (node (ref "UD1") (pin "T12") (pinfunction "VSS41_T12") (pintype "input"))
      (node (ref "UD1") (pin "T3") (pinfunction "VSS37_T3") (pintype "input"))
      (node (ref "UD1") (pin "T5") (pinfunction "VSS38_T5") (pintype "input"))
      (node (ref "UD1") (pin "T8") (pinfunction "VSS39_T8") (pintype "input"))
      (node (ref "UD1") (pin "V1") (pinfunction "VSS42_V1") (pintype "input"))
      (node (ref "UD1") (pin "V12") (pinfunction "VSS45_V12") (pintype "input"))
      (node (ref "UD1") (pin "V5") (pinfunction "VSS43_V5") (pintype "input"))
      (node (ref "UD1") (pin "V8") (pinfunction "VSS44_V8") (pintype "input"))
      (node (ref "UD1") (pin "W11") (pinfunction "VSS49_W11") (pintype "input"))
      (node (ref "UD1") (pin "W2") (pinfunction "VSS46_W2") (pintype "input"))
      (node (ref "UD1") (pin "W4") (pinfunction "VSS47_W4") (pintype "input"))
      (node (ref "UD1") (pin "W9") (pinfunction "VSS48_W9") (pintype "input"))
      (node (ref "UD1") (pin "Y1") (pinfunction "VSS50_Y1") (pintype "input"))
      (node (ref "UD1") (pin "Y12") (pinfunction "VSS53_Y12") (pintype "input"))
      (node (ref "UD1") (pin "Y5") (pinfunction "VSS51_Y5") (pintype "input"))
      (node (ref "UD1") (pin "Y8") (pinfunction "VSS52_Y8") (pintype "input"))
    )
    (net (code "71") (name "Net-(U1A-SZQ)") (class "Default")
      (node (ref "R3") (pin "1") (pinfunction "1_1") (pintype "input"))
      (node (ref "U1") (pin "AA29") (pinfunction "SZQ_AA29") (pintype "input"))
    )
    (net (code "72") (name "Net-(UD1A-ODT_CA_A)") (class "Default")
      (node (ref "R1") (pin "1") (pinfunction "1_1") (pintype "input"))
      (node (ref "UD1") (pin "G2") (pinfunction "ODT_CA_A_G2") (pintype "input"))
    )
    (net (code "73") (name "Net-(UD1A-ODT_CA_B)") (class "Default")
      (node (ref "R2") (pin "1") (pinfunction "1_1") (pintype "input"))
      (node (ref "UD1") (pin "T2") (pinfunction "ODT_CA_B_T2") (pintype "input"))
    )
    (net (code "74") (name "Net-(UD1A-ZQ0)") (class "Default")
      (node (ref "R4") (pin "1") (pinfunction "1_1") (pintype "input"))
      (node (ref "UD1") (pin "A5") (pinfunction "ZQ0_A5") (pintype "input"))
    )
    (net (code "75") (name "Net-(UD1A-ZQ1)") (class "Default")
      (node (ref "R5") (pin "1") (pinfunction "1_1") (pintype "input"))
      (node (ref "UD1") (pin "A8") (pinfunction "ZQ1_A8") (pintype "input"))
    )
    (net (code "76") (name "VCC-DRAM") (class "Default")
      (node (ref "C1") (pin "1") (pinfunction "1_1") (pintype "input"))
      (node (ref "C14") (pin "1") (pinfunction "1_1") (pintype "input"))
      (node (ref "C15") (pin "1") (pinfunction "1_1") (pintype "input"))
      (node (ref "C16") (pin "2") (pinfunction "2_2") (pintype "input"))
      (node (ref "C17") (pin "2") (pinfunction "2_2") (pintype "input"))
      (node (ref "C18") (pin "2") (pinfunction "2_2") (pintype "input"))
      (node (ref "C19") (pin "1") (pinfunction "1_1") (pintype "input"))
      (node (ref "C2") (pin "1") (pinfunction "1_1") (pintype "input"))
      (node (ref "C20") (pin "2") (pinfunction "2_2") (pintype "input"))
      (node (ref "C21") (pin "2") (pinfunction "2_2") (pintype "input"))
      (node (ref "C22") (pin "2") (pinfunction "2_2") (pintype "input"))
      (node (ref "C23") (pin "2") (pinfunction "2_2") (pintype "input"))
      (node (ref "C24") (pin "2") (pinfunction "2_2") (pintype "input"))
      (node (ref "C25") (pin "2") (pinfunction "2_2") (pintype "input"))
      (node (ref "C26") (pin "2") (pinfunction "2_2") (pintype "input"))
      (node (ref "C3") (pin "2") (pinfunction "2_2") (pintype "input"))
      (node (ref "C4") (pin "2") (pinfunction "2_2") (pintype "input"))
      (node (ref "C5") (pin "2") (pinfunction "2_2") (pintype "input"))
      (node (ref "R1") (pin "2") (pinfunction "2_2") (pintype "input"))
      (node (ref "R2") (pin "2") (pinfunction "2_2") (pintype "input"))
      (node (ref "R3") (pin "2") (pinfunction "2_2") (pintype "input"))
      (node (ref "R4") (pin "2") (pinfunction "2_2") (pintype "input"))
      (node (ref "R5") (pin "2") (pinfunction "2_2") (pintype "input"))
      (node (ref "U1") (pin "AA24") (pinfunction "VCC-DRAM4_AA24") (pintype "input"))
      (node (ref "U1") (pin "AB24") (pinfunction "VCC-DRAM5_AB24") (pintype "input"))
      (node (ref "U1") (pin "AC17") (pinfunction "VCC-DRAML0_AC17") (pintype "input"))
      (node (ref "U1") (pin "AC18") (pinfunction "VCC-DRAML1_AC18") (pintype "input"))
      (node (ref "U1") (pin "AC19") (pinfunction "VCC-DRAML2_AC19") (pintype "input"))
      (node (ref "U1") (pin "AC20") (pinfunction "VCC-DRAML3_AC20") (pintype "input"))
      (node (ref "U1") (pin "AC22") (pinfunction "VCC-DRAML4_AC22") (pintype "input"))
      (node (ref "U1") (pin "AC24") (pinfunction "VCC-DRAM6_AC24") (pintype "input"))
      (node (ref "U1") (pin "W23") (pinfunction "VCC-DRAM0_W23") (pintype "input"))
      (node (ref "U1") (pin "W24") (pinfunction "VCC-DRAM1_W24") (pintype "input"))
      (node (ref "U1") (pin "W25") (pinfunction "VCC-DRAM2_W25") (pintype "input"))
      (node (ref "U1") (pin "Y24") (pinfunction "VCC-DRAM3_Y24") (pintype "input"))
      (node (ref "UD1") (pin "A4") (pinfunction "VDD2-0_A4") (pintype "input"))
      (node (ref "UD1") (pin "A9") (pinfunction "VDD2-1_A9") (pintype "input"))
      (node (ref "UD1") (pin "AA10") (pinfunction "VDDQ-19_AA10") (pintype "input"))
      (node (ref "UD1") (pin "AA3") (pinfunction "VDDQ-16_AA3") (pintype "input"))
      (node (ref "UD1") (pin "AA5") (pinfunction "VDDQ-17_AA5") (pintype "input"))
      (node (ref "UD1") (pin "AA8") (pinfunction "VDDQ-18_AA8") (pintype "input"))
      (node (ref "UD1") (pin "AB4") (pinfunction "VDD2-22_AB4") (pintype "input"))
      (node (ref "UD1") (pin "AB9") (pinfunction "VDD2-23_AB9") (pintype "input"))
      (node (ref "UD1") (pin "B10") (pinfunction "VDDQ-3_B10") (pintype "input"))
      (node (ref "UD1") (pin "B3") (pinfunction "VDDQ-0_B3") (pintype "input"))
      (node (ref "UD1") (pin "B5") (pinfunction "VDDQ-1_B5") (pintype "input"))
      (node (ref "UD1") (pin "B8") (pinfunction "VDDQ-2_B8") (pintype "input"))
      (node (ref "UD1") (pin "D1") (pinfunction "VDDQ-4_D1") (pintype "input"))
      (node (ref "UD1") (pin "D12") (pinfunction "VDDQ-7_D12") (pintype "input"))
      (node (ref "UD1") (pin "D5") (pinfunction "VDDQ-5_D5") (pintype "input"))
      (node (ref "UD1") (pin "D8") (pinfunction "VDDQ-6_D8") (pintype "input"))
      (node (ref "UD1") (pin "F10") (pinfunction "VDDQ-9_F10") (pintype "input"))
      (node (ref "UD1") (pin "F3") (pinfunction "VDDQ-8_F3") (pintype "input"))
      (node (ref "UD1") (pin "F5") (pinfunction "VDD2-2_F5") (pintype "input"))
      (node (ref "UD1") (pin "F8") (pinfunction "VDD2-3_F8") (pintype "input"))
      (node (ref "UD1") (pin "H1") (pinfunction "VDD2-4_H1") (pintype "input"))
      (node (ref "UD1") (pin "H12") (pinfunction "VDD2-7_H12") (pintype "input"))
      (node (ref "UD1") (pin "H5") (pinfunction "VDD2-5_H5") (pintype "input"))
      (node (ref "UD1") (pin "H8") (pinfunction "VDD2-6_H8") (pintype "input"))
      (node (ref "UD1") (pin "K1") (pinfunction "VDD2-8_K1") (pintype "input"))
      (node (ref "UD1") (pin "K10") (pinfunction "VDD2-10_K10") (pintype "input"))
      (node (ref "UD1") (pin "K12") (pinfunction "VDD2-11_K12") (pintype "input"))
      (node (ref "UD1") (pin "K3") (pinfunction "VDD2-9_K3") (pintype "input"))
      (node (ref "UD1") (pin "N1") (pinfunction "VDD2-12_N1") (pintype "input"))
      (node (ref "UD1") (pin "N10") (pinfunction "VDD2-14_N10") (pintype "input"))
      (node (ref "UD1") (pin "N12") (pinfunction "VDD2-15_N12") (pintype "input"))
      (node (ref "UD1") (pin "N3") (pinfunction "VDD2-13_N3") (pintype "input"))
      (node (ref "UD1") (pin "R1") (pinfunction "VDD2-16_R1") (pintype "input"))
      (node (ref "UD1") (pin "R12") (pinfunction "VDD2-19_R12") (pintype "input"))
      (node (ref "UD1") (pin "R5") (pinfunction "VDD2-17_R5") (pintype "input"))
      (node (ref "UD1") (pin "R8") (pinfunction "VDD2-18_R8") (pintype "input"))
      (node (ref "UD1") (pin "U10") (pinfunction "VDDQ-11_U10") (pintype "input"))
      (node (ref "UD1") (pin "U3") (pinfunction "VDDQ-10_U3") (pintype "input"))
      (node (ref "UD1") (pin "U5") (pinfunction "VDD2-20_U5") (pintype "input"))
      (node (ref "UD1") (pin "U8") (pinfunction "VDD2-21_U8") (pintype "input"))
      (node (ref "UD1") (pin "W1") (pinfunction "VDDQ-12_W1") (pintype "input"))
      (node (ref "UD1") (pin "W12") (pinfunction "VDDQ-15_W12") (pintype "input"))
      (node (ref "UD1") (pin "W5") (pinfunction "VDDQ-13_W5") (pintype "input"))
      (node (ref "UD1") (pin "W8") (pinfunction "VDDQ-14_W8") (pintype "input"))
    )
    (net (code "77") (name "VDD18-DRAM") (class "Default")
      (node (ref "C27") (pin "1") (pinfunction "1_1") (pintype "input"))
      (node (ref "C28") (pin "2") (pinfunction "2_2") (pintype "input"))
      (node (ref "C6") (pin "1") (pinfunction "1_1") (pintype "input"))
      (node (ref "C7") (pin "2") (pinfunction "2_2") (pintype "input"))
      (node (ref "U1") (pin "AD25") (pinfunction "VDD18-DRAM_AD25") (pintype "input"))
    )
    (net (code "78") (name "VDD18-LPDDR") (class "Default")
      (node (ref "C10") (pin "2") (pinfunction "2_2") (pintype "input"))
      (node (ref "C11") (pin "2") (pinfunction "2_2") (pintype "input"))
      (node (ref "C12") (pin "2") (pinfunction "2_2") (pintype "input"))
      (node (ref "C13") (pin "2") (pinfunction "2_2") (pintype "input"))
      (node (ref "C8") (pin "1") (pinfunction "1_1") (pintype "input"))
      (node (ref "C9") (pin "2") (pinfunction "2_2") (pintype "input"))
      (node (ref "UD1") (pin "F1") (pinfunction "VDD1-0_F1") (pintype "input"))
      (node (ref "UD1") (pin "F12") (pinfunction "VDD1-1_F12") (pintype "input"))
      (node (ref "UD1") (pin "G4") (pinfunction "VDD1-2_G4") (pintype "input"))
      (node (ref "UD1") (pin "G9") (pinfunction "VDD1-3_G9") (pintype "input"))
      (node (ref "UD1") (pin "T4") (pinfunction "VDD1-4_T4") (pintype "input"))
      (node (ref "UD1") (pin "T9") (pinfunction "VDD1-5_T9") (pintype "input"))
      (node (ref "UD1") (pin "U1") (pinfunction "VDD1-6_U1") (pintype "input"))
      (node (ref "UD1") (pin "U12") (pinfunction "VDD1-7_U12") (pintype "input"))
    )
    (net (code "79") (name "unconnected-(U1A-SA0-PadAK33)") (class "Default")
      (node (ref "U1") (pin "AK33") (pinfunction "SA0_AK33") (pintype "input+no_connect"))
    )
    (net (code "80") (name "unconnected-(U1A-SA3-PadAL27)") (class "Default")
      (node (ref "U1") (pin "AL27") (pinfunction "SA3_AL27") (pintype "input+no_connect"))
    )
    (net (code "81") (name "unconnected-(U1A-SA7-PadAM33)") (class "Default")
      (node (ref "U1") (pin "AM33") (pinfunction "SA7_AM33") (pintype "input+no_connect"))
    )
    (net (code "82") (name "unconnected-(U1A-SBG0-PadAN26)") (class "Default")
      (node (ref "U1") (pin "AN26") (pinfunction "SBG0_AN26") (pintype "input+no_connect"))
    )
    (net (code "83") (name "unconnected-(U1A-SODT0-PadAL32)") (class "Default")
      (node (ref "U1") (pin "AL32") (pinfunction "SODT0_AL32") (pintype "input+no_connect"))
    )
    (net (code "84") (name "unconnected-(U1A-SODT1-PadAL33)") (class "Default")
      (node (ref "U1") (pin "AL33") (pinfunction "SODT1_AL33") (pintype "input+no_connect"))
    )
    (net (code "85") (name "unconnected-(UD1B-NC0-PadA1)") (class "Default")
      (node (ref "UD1") (pin "A1") (pinfunction "NC0_A1") (pintype "input+no_connect"))
    )
    (net (code "86") (name "unconnected-(UD1B-NC1-PadA2)") (class "Default")
      (node (ref "UD1") (pin "A2") (pinfunction "NC1_A2") (pintype "input+no_connect"))
    )
    (net (code "87") (name "unconnected-(UD1B-NC2-PadA11)") (class "Default")
      (node (ref "UD1") (pin "A11") (pinfunction "NC2_A11") (pintype "input+no_connect"))
    )
    (net (code "88") (name "unconnected-(UD1B-NC3-PadA12)") (class "Default")
      (node (ref "UD1") (pin "A12") (pinfunction "NC3_A12") (pintype "input+no_connect"))
    )
    (net (code "89") (name "unconnected-(UD1B-NC4-PadB1)") (class "Default")
      (node (ref "UD1") (pin "B1") (pinfunction "NC4_B1") (pintype "input+no_connect"))
    )
    (net (code "90") (name "unconnected-(UD1B-NC5-PadB12)") (class "Default")
      (node (ref "UD1") (pin "B12") (pinfunction "NC5_B12") (pintype "input+no_connect"))
    )
    (net (code "91") (name "unconnected-(UD1B-NC6-PadG11)") (class "Default")
      (node (ref "UD1") (pin "G11") (pinfunction "NC6_G11") (pintype "input+no_connect"))
    )
    (net (code "92") (name "unconnected-(UD1B-NC7-PadK5)") (class "Default")
      (node (ref "UD1") (pin "K5") (pinfunction "NC7_K5") (pintype "input+no_connect"))
    )
    (net (code "93") (name "unconnected-(UD1B-NC8-PadK8)") (class "Default")
      (node (ref "UD1") (pin "K8") (pinfunction "NC8_K8") (pintype "input+no_connect"))
    )
    (net (code "94") (name "unconnected-(UD1B-NC9-PadN5)") (class "Default")
      (node (ref "UD1") (pin "N5") (pinfunction "NC9_N5") (pintype "input+no_connect"))
    )
    (net (code "95") (name "unconnected-(UD1B-NC10-PadN8)") (class "Default")
      (node (ref "UD1") (pin "N8") (pinfunction "NC10_N8") (pintype "input+no_connect"))
    )
    (net (code "96") (name "unconnected-(UD1B-NC11-PadAA1)") (class "Default")
      (node (ref "UD1") (pin "AA1") (pinfunction "NC11_AA1") (pintype "input+no_connect"))
    )
    (net (code "97") (name "unconnected-(UD1B-NC12-PadAA12)") (class "Default")
      (node (ref "UD1") (pin "AA12") (pinfunction "NC12_AA12") (pintype "input+no_connect"))
    )
    (net (code "98") (name "unconnected-(UD1B-NC13-PadAB1)") (class "Default")
      (node (ref "UD1") (pin "AB1") (pinfunction "NC13_AB1") (pintype "input+no_connect"))
    )
    (net (code "99") (name "unconnected-(UD1B-NC14-PadAB2)") (class "Default")
      (node (ref "UD1") (pin "AB2") (pinfunction "NC14_AB2") (pintype "input+no_connect"))
    )
    (net (code "100") (name "unconnected-(UD1B-NC15-PadAB11)") (class "Default")
      (node (ref "UD1") (pin "AB11") (pinfunction "NC15_AB11") (pintype "input+no_connect"))
    )
    (net (code "101") (name "unconnected-(UD1B-NC16-PadAB12)") (class "Default")
      (node (ref "UD1") (pin "AB12") (pinfunction "NC16_AB12") (pintype "input+no_connect"))
    )
  )
)
